# RefloLeo_v1_3.net
KiCad netlist of a schematic drawn in EAGLE
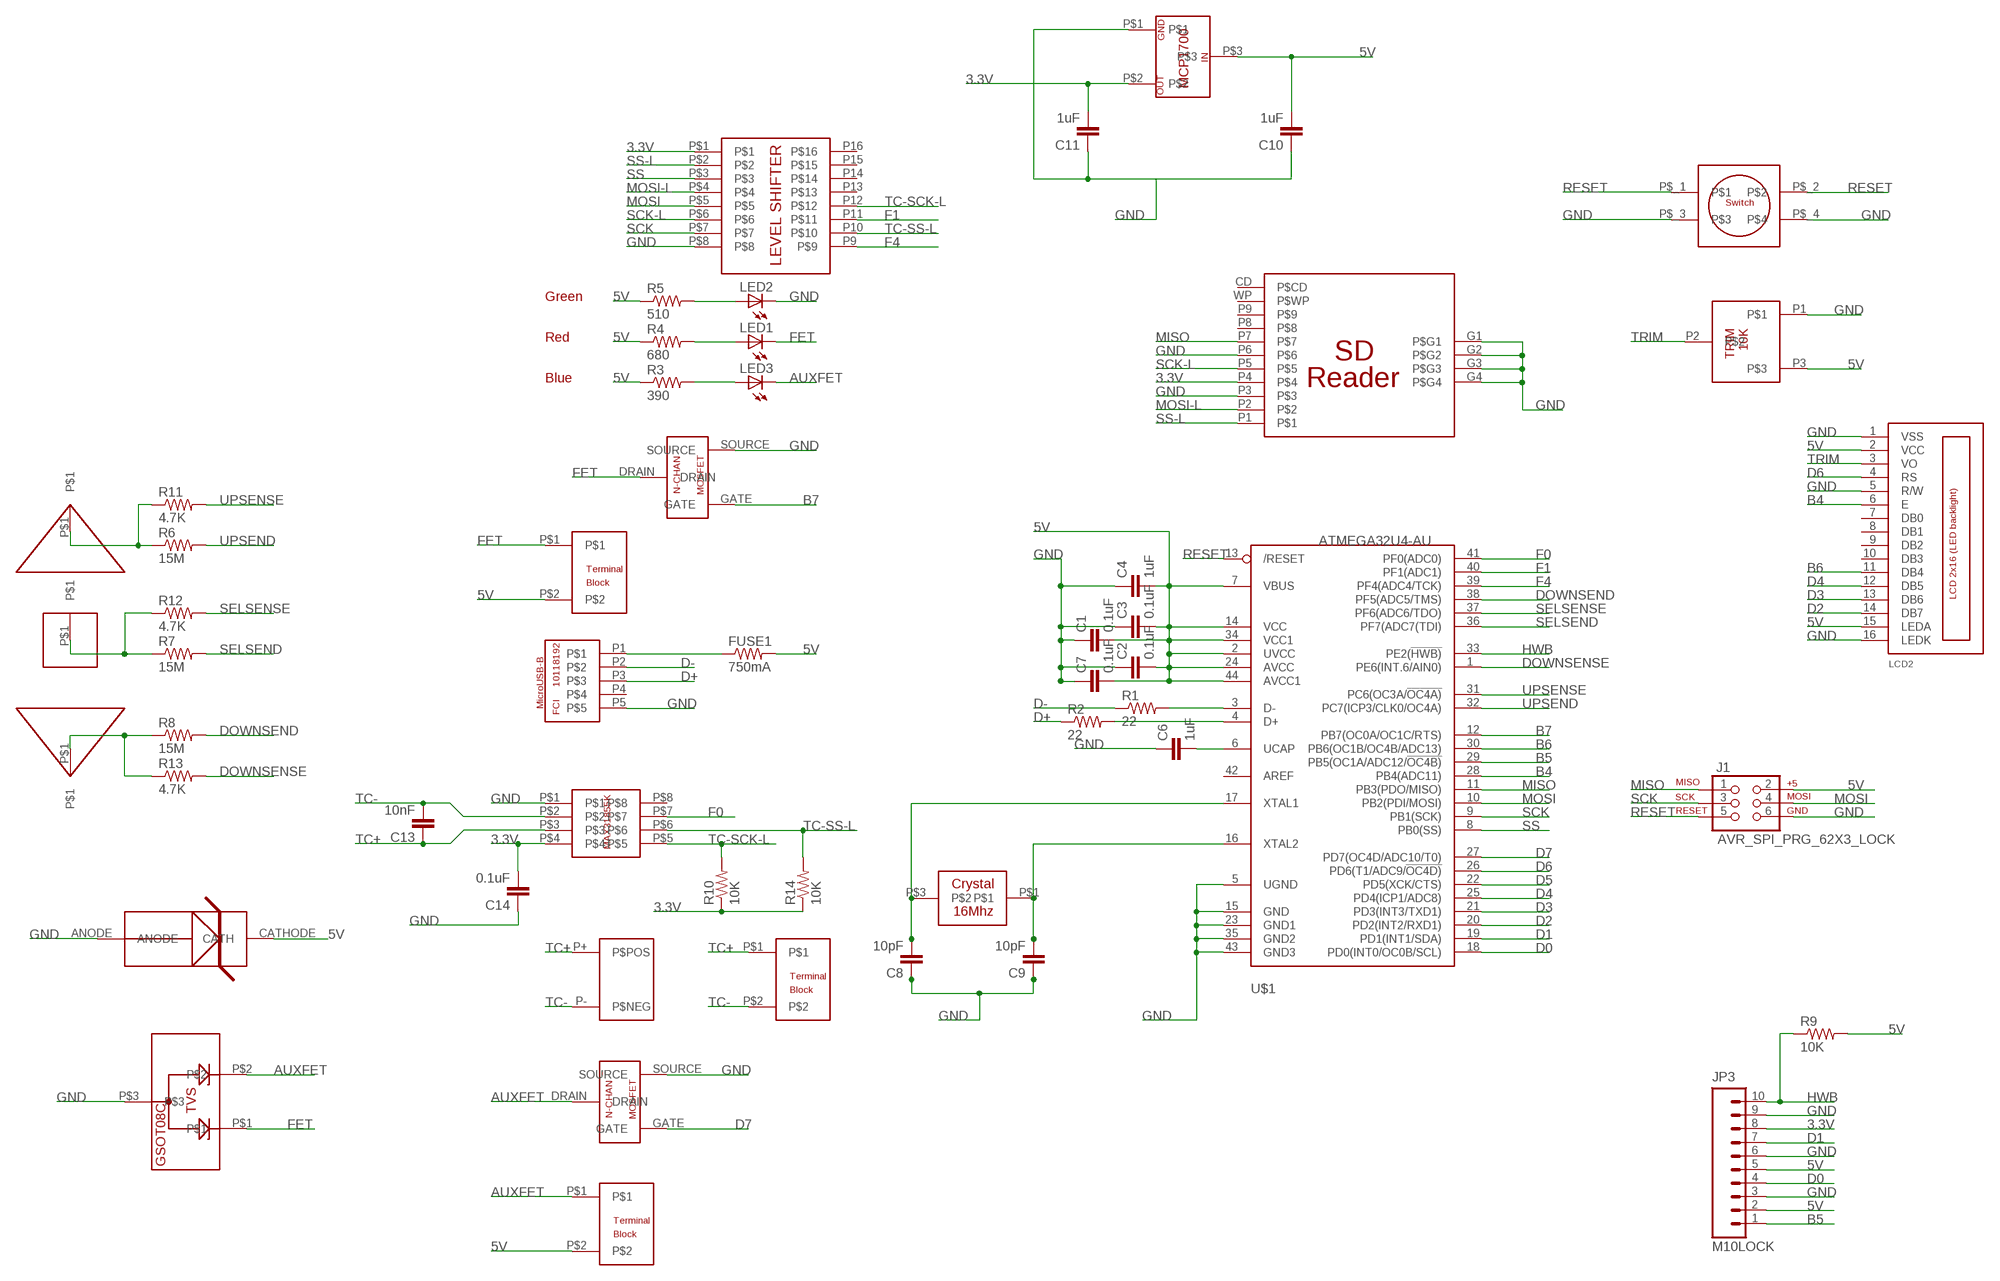
[diagram p0: schematic, sheet 1]

(export (version "E")
  (design (tool "Eeschema 10.0.6"))
  (components
    (comp (ref "C1")
      (value "0.1uF")
      (footprint "eagle-import:0603-CAP")
      (libsource (lib "eagle-import") (part "CAP0603-CAP"))
    )
    (comp (ref "C2")
      (value "0.1uF")
      (footprint "eagle-import:0603-CAP")
      (libsource (lib "eagle-import") (part "CAP0603-CAP"))
    )
    (comp (ref "C3")
      (value "0.1uF")
      (footprint "eagle-import:0603-CAP")
      (libsource (lib "eagle-import") (part "CAP0603-CAP"))
    )
    (comp (ref "C4")
      (value "1uF")
      (footprint "eagle-import:0603-CAP")
      (libsource (lib "eagle-import") (part "CAP0603-CAP"))
    )
    (comp (ref "C6")
      (value "1uF")
      (footprint "eagle-import:0603-CAP")
      (libsource (lib "eagle-import") (part "CAP0603-CAP"))
    )
    (comp (ref "C7")
      (value "0.1uF")
      (footprint "eagle-import:0603-CAP")
      (libsource (lib "eagle-import") (part "CAP0603-CAP"))
    )
    (comp (ref "C8")
      (value "10pF")
      (footprint "eagle-import:0603-CAP")
      (libsource (lib "eagle-import") (part "CAP0603-CAP"))
    )
    (comp (ref "C9")
      (value "10pF")
      (footprint "eagle-import:0603-CAP")
      (libsource (lib "eagle-import") (part "CAP0603-CAP"))
    )
    (comp (ref "C10")
      (value "1uF")
      (footprint "eagle-import:0603-CAP")
      (libsource (lib "eagle-import") (part "CAP0603-CAP"))
    )
    (comp (ref "C11")
      (value "1uF")
      (footprint "eagle-import:0603-CAP")
      (libsource (lib "eagle-import") (part "CAP0603-CAP"))
    )
    (comp (ref "C13")
      (value "10nF")
      (footprint "eagle-import:0603-CAP")
      (libsource (lib "eagle-import") (part "CAP0603-CAP"))
    )
    (comp (ref "C14")
      (value "0.1uF")
      (footprint "eagle-import:0603-CAP")
      (libsource (lib "eagle-import") (part "CAP0603-CAP"))
    )
    (comp (ref "FUSE1")
      (value "750mA")
      (footprint "eagle-import:0603-RES")
      (libsource (lib "eagle-import") (part "RESISTOR0603-RES"))
    )
    (comp (ref "J1")
      (value "AVR_SPI_PRG_62X3_LOCK")
      (footprint "eagle-import:2X3_LOCK")
      (libsource (lib "eagle-import") (part "AVR_SPI_PRG_62X3_LOCK"))
    )
    (comp (ref "JP3")
      (value "M10LOCK")
      (footprint "eagle-import:1X10_LOCK")
      (libsource (lib "eagle-import") (part "M10LOCK"))
    )
    (comp (ref "LCD2")
      (value "LCD_2X16_SIL")
      (footprint "eagle-import:HY-1602F")
      (libsource (lib "eagle-import") (part "LCD_2X16_SIL"))
    )
    (comp (ref "LED1")
      (value "LED0603")
      (footprint "eagle-import:LED-0603")
      (libsource (lib "eagle-import") (part "LED0603"))
    )
    (comp (ref "LED2")
      (value "LED0603")
      (footprint "eagle-import:LED-0603")
      (libsource (lib "eagle-import") (part "LED0603"))
    )
    (comp (ref "LED3")
      (value "LED0603")
      (footprint "eagle-import:LED-0603")
      (libsource (lib "eagle-import") (part "LED0603"))
    )
    (comp (ref "R1")
      (value "22")
      (footprint "eagle-import:0603-RES")
      (libsource (lib "eagle-import") (part "RESISTOR0603-RES"))
    )
    (comp (ref "R2")
      (value "22")
      (footprint "eagle-import:0603-RES")
      (libsource (lib "eagle-import") (part "RESISTOR0603-RES"))
    )
    (comp (ref "R3")
      (value "390")
      (footprint "eagle-import:0603-RES")
      (libsource (lib "eagle-import") (part "RESISTOR0603-RES"))
    )
    (comp (ref "R4")
      (value "680")
      (footprint "eagle-import:0603-RES")
      (libsource (lib "eagle-import") (part "RESISTOR0603-RES"))
    )
    (comp (ref "R5")
      (value "510")
      (footprint "eagle-import:0603-RES")
      (libsource (lib "eagle-import") (part "RESISTOR0603-RES"))
    )
    (comp (ref "R6")
      (value "15M")
      (footprint "eagle-import:0603-RES")
      (libsource (lib "eagle-import") (part "RESISTOR0603-RES"))
    )
    (comp (ref "R7")
      (value "15M")
      (footprint "eagle-import:0603-RES")
      (libsource (lib "eagle-import") (part "RESISTOR0603-RES"))
    )
    (comp (ref "R8")
      (value "15M")
      (footprint "eagle-import:0603-RES")
      (libsource (lib "eagle-import") (part "RESISTOR0603-RES"))
    )
    (comp (ref "R9")
      (value "10K")
      (footprint "eagle-import:0603-RES")
      (libsource (lib "eagle-import") (part "RESISTOR0603-RES"))
    )
    (comp (ref "R10")
      (value "10K")
      (footprint "eagle-import:0603-RES")
      (libsource (lib "eagle-import") (part "RESISTOR0603-RES"))
    )
    (comp (ref "R11")
      (value "4.7K")
      (footprint "eagle-import:0603-RES")
      (libsource (lib "eagle-import") (part "RESISTOR0603-RES"))
    )
    (comp (ref "R12")
      (value "4.7K")
      (footprint "eagle-import:0603-RES")
      (libsource (lib "eagle-import") (part "RESISTOR0603-RES"))
    )
    (comp (ref "R13")
      (value "4.7K")
      (footprint "eagle-import:0603-RES")
      (libsource (lib "eagle-import") (part "RESISTOR0603-RES"))
    )
    (comp (ref "R14")
      (value "10K")
      (footprint "eagle-import:0603-RES")
      (libsource (lib "eagle-import") (part "RESISTOR0603-RES"))
    )
    (comp (ref "U$1")
      (value "ATMEGA32U4-AU")
      (footprint "eagle-import:TQFP44")
      (libsource (lib "eagle-import") (part "ATMEGA32U4-AU"))
    )
    (comp (ref "U$2")
      (value "16MHZ-CRYSTAL_NX3225GA-16.000M-STD-CRG-1")
      (footprint "eagle-import:16MHZ-CRYSTAL_NX3225GA-16.000M-STD-CRG-1")
      (libsource (lib "eagle-import") (part "16MHZ-CRYSTAL_NX3225GA-16.000M-STD-CRG-1"))
    )
    (comp (ref "U$3")
      (value "USB-B_10118192-0001LF")
      (footprint "eagle-import:USB-B_10118192-0001LF")
      (libsource (lib "eagle-import") (part "USB-B_10118192-0001LF"))
    )
    (comp (ref "U$4")
      (value "SDREADER_2041021-4")
      (footprint "eagle-import:SDREADER_2041021-4")
      (libsource (lib "eagle-import") (part "SDREADER_2041021-4"))
    )
    (comp (ref "U$5")
      (value "2POS_TERM_ED2748-ND")
      (footprint "eagle-import:2POS_TERM_ED2748-ND")
      (libsource (lib "eagle-import") (part "2POS_TERM_ED2748-ND"))
    )
    (comp (ref "U$6")
      (value "N-MOSFET630_DMG1012T-7DICT-ND")
      (footprint "eagle-import:N-MOSFET630_DMG1012T-7DICT-ND")
      (libsource (lib "eagle-import") (part "N-MOSFET630_DMG1012T-7DICT-ND"))
    )
    (comp (ref "U$7")
      (value "2POS_TERM_ED2748-ND")
      (footprint "eagle-import:2POS_TERM_ED2748-ND")
      (libsource (lib "eagle-import") (part "2POS_TERM_ED2748-ND"))
    )
    (comp (ref "U$8")
      (value "NXP_LVL_SHIFT_74HC4050D,653")
      (footprint "eagle-import:NXP_LVL_SHIFT_74HC4050D,653")
      (libsource (lib "eagle-import") (part "NXP_LVL_SHIFT_74HC4050D,653"))
    )
    (comp (ref "U$9")
      (value "MAX_TC_MAX31855KASA+")
      (footprint "eagle-import:MAX_TC_MAX31855KASA+")
      (libsource (lib "eagle-import") (part "MAX_TC_MAX31855KASA+"))
    )
    (comp (ref "U$10")
      (value "10K_TRIM_3362F-1-103LF")
      (footprint "eagle-import:10K_TRIM_3362F-1-103LF")
      (libsource (lib "eagle-import") (part "10K_TRIM_3362F-1-103LF"))
    )
    (comp (ref "U$11")
      (value "MCP1700__LDO")
      (footprint "eagle-import:MCP1700__LDO")
      (libsource (lib "eagle-import") (part "MCP1700__LDO"))
    )
    (comp (ref "U$12")
      (value "MOM-SWITCH-EG4620CT-ND")
      (footprint "eagle-import:MOM-SWITCH-EG4620CT-ND")
      (libsource (lib "eagle-import") (part "MOM-SWITCH-EG4620CT-ND"))
    )
    (comp (ref "U$13")
      (value "CAPTOUCH_ARROW")
      (footprint "eagle-import:CAPTOUCH_ARROW")
      (libsource (lib "eagle-import") (part "CAPTOUCH_ARROW"))
    )
    (comp (ref "U$14")
      (value "CAPTOUCH_ARROW")
      (footprint "eagle-import:CAPTOUCH_ARROW")
      (libsource (lib "eagle-import") (part "CAPTOUCH_ARROW"))
    )
    (comp (ref "U$15")
      (value "CAPTOUCH_SQUARE")
      (footprint "eagle-import:CAPTOUCH_SQUARE")
      (libsource (lib "eagle-import") (part "CAPTOUCH_SQUARE"))
    )
    (comp (ref "U$16")
      (value "N-MOSFET630_DMG1012T-7DICT-ND")
      (footprint "eagle-import:N-MOSFET630_DMG1012T-7DICT-ND")
      (libsource (lib "eagle-import") (part "N-MOSFET630_DMG1012T-7DICT-ND"))
    )
    (comp (ref "U$17")
      (value "2POS_TERM_ED2748-ND")
      (footprint "eagle-import:2POS_TERM_ED2748-ND")
      (libsource (lib "eagle-import") (part "2POS_TERM_ED2748-ND"))
    )
    (comp (ref "U$18")
      (value "TVS_DIODE_MATRIX_GSOT08C-GS08")
      (footprint "eagle-import:TVS_DIODE_MATRIX_GSOT08C-GS08")
      (libsource (lib "eagle-import") (part "TVS_DIODE_MATRIX_GSOT08C-GS08"))
    )
    (comp (ref "U$19")
      (value "TVS_DIODE_1CH_1SMB6.0AT3G")
      (footprint "eagle-import:TVS_DIODE_1CH_1SMB6.0AT3G")
      (libsource (lib "eagle-import") (part "TVS_DIODE_1CH_1SMB6.0AT3G"))
    )
    (comp (ref "U$20")
      (value "CUSTOM_K-TYPE")
      (footprint "eagle-import:CUSTOM_K-TYPE")
      (libsource (lib "eagle-import") (part "CUSTOM_K-TYPE"))
    )
  )
  (nets
    (net (code "1") (name "/3.3V") (class "Default")
      (node (ref "C11") (pin "2") (pinfunction "2_2") (pintype "passive"))
      (node (ref "C14") (pin "2") (pinfunction "2_2") (pintype "passive"))
      (node (ref "JP3") (pin "8") (pinfunction "8_8") (pintype "passive"))
      (node (ref "R10") (pin "1") (pinfunction "1_1") (pintype "passive"))
      (node (ref "R14") (pin "1") (pinfunction "1_1") (pintype "passive"))
      (node (ref "U$11") (pin "P$2") (pinfunction "P$2_P$2") (pintype "bidirectional"))
      (node (ref "U$4") (pin "P4") (pinfunction "P$4_P4") (pintype "bidirectional"))
      (node (ref "U$8") (pin "P$1") (pinfunction "P$1_P$1") (pintype "bidirectional"))
      (node (ref "U$9") (pin "P$4") (pinfunction "P$4_P$4") (pintype "bidirectional"))
    )
    (net (code "2") (name "/5V") (class "Default")
      (node (ref "C1") (pin "2") (pinfunction "2_2") (pintype "passive"))
      (node (ref "C10") (pin "2") (pinfunction "2_2") (pintype "passive"))
      (node (ref "C2") (pin "2") (pinfunction "2_2") (pintype "passive"))
      (node (ref "C3") (pin "2") (pinfunction "2_2") (pintype "passive"))
      (node (ref "C4") (pin "2") (pinfunction "2_2") (pintype "passive"))
      (node (ref "C7") (pin "2") (pinfunction "2_2") (pintype "passive"))
      (node (ref "FUSE1") (pin "2") (pinfunction "2_2") (pintype "passive"))
      (node (ref "J1") (pin "2") (pinfunction "2_2") (pintype "passive"))
      (node (ref "JP3") (pin "2") (pinfunction "2_2") (pintype "passive"))
      (node (ref "JP3") (pin "5") (pinfunction "5_5") (pintype "passive"))
      (node (ref "LCD2") (pin "15") (pinfunction "LEDA_15") (pintype "passive"))
      (node (ref "LCD2") (pin "2") (pinfunction "VCC_2") (pintype "power_in"))
      (node (ref "R3") (pin "1") (pinfunction "1_1") (pintype "passive"))
      (node (ref "R4") (pin "1") (pinfunction "1_1") (pintype "passive"))
      (node (ref "R5") (pin "1") (pinfunction "1_1") (pintype "passive"))
      (node (ref "R9") (pin "2") (pinfunction "2_2") (pintype "passive"))
      (node (ref "U$1") (pin "14") (pinfunction "VCC_14") (pintype "bidirectional"))
      (node (ref "U$1") (pin "2") (pinfunction "UVCC_2") (pintype "bidirectional"))
      (node (ref "U$1") (pin "24") (pinfunction "AVCC_24") (pintype "bidirectional"))
      (node (ref "U$1") (pin "34") (pinfunction "VCC1_34") (pintype "bidirectional"))
      (node (ref "U$1") (pin "44") (pinfunction "AVCC1_44") (pintype "bidirectional"))
      (node (ref "U$1") (pin "7") (pinfunction "VBUS_7") (pintype "bidirectional"))
      (node (ref "U$10") (pin "P3") (pinfunction "P$3_P3") (pintype "bidirectional"))
      (node (ref "U$11") (pin "P$3") (pinfunction "P$3_P$3") (pintype "bidirectional"))
      (node (ref "U$17") (pin "P$2") (pinfunction "P$2_P$2") (pintype "bidirectional"))
      (node (ref "U$19") (pin "CATHODE") (pinfunction "CATH_CATHODE") (pintype "bidirectional"))
      (node (ref "U$5") (pin "P$2") (pinfunction "P$2_P$2") (pintype "bidirectional"))
    )
    (net (code "3") (name "/AUXFET") (class "Default")
      (node (ref "LED3") (pin "C") (pinfunction "C_C") (pintype "passive"))
      (node (ref "U$16") (pin "DRAIN") (pinfunction "DRAIN_DRAIN") (pintype "bidirectional"))
      (node (ref "U$17") (pin "P$1") (pinfunction "P$1_P$1") (pintype "bidirectional"))
      (node (ref "U$18") (pin "P$2") (pinfunction "P$2_P$2") (pintype "bidirectional"))
    )
    (net (code "4") (name "/B4") (class "Default")
      (node (ref "LCD2") (pin "6") (pinfunction "E_6") (pintype "input"))
      (node (ref "U$1") (pin "28") (pinfunction "PB4(ADC11)_28") (pintype "bidirectional"))
    )
    (net (code "5") (name "/B5") (class "Default")
      (node (ref "JP3") (pin "1") (pinfunction "1_1") (pintype "passive"))
      (node (ref "U$1") (pin "29") (pinfunction "PB5(OC1A/ADC12/~{OC4B})_29") (pintype "bidirectional"))
    )
    (net (code "6") (name "/B6") (class "Default")
      (node (ref "LCD2") (pin "11") (pinfunction "DB4_11") (pintype "bidirectional"))
      (node (ref "U$1") (pin "30") (pinfunction "PB6(OC1B/OC4B/ADC13)_30") (pintype "bidirectional"))
    )
    (net (code "7") (name "/B7") (class "Default")
      (node (ref "U$1") (pin "12") (pinfunction "PB7(OC0A/OC1C/RTS)_12") (pintype "bidirectional"))
      (node (ref "U$6") (pin "GATE") (pinfunction "GATE_GATE") (pintype "bidirectional"))
    )
    (net (code "8") (name "/D+") (class "Default")
      (node (ref "R2") (pin "1") (pinfunction "1_1") (pintype "passive"))
      (node (ref "U$3") (pin "P3") (pinfunction "P$3_P3") (pintype "bidirectional"))
    )
    (net (code "9") (name "/D-") (class "Default")
      (node (ref "R1") (pin "1") (pinfunction "1_1") (pintype "passive"))
      (node (ref "U$3") (pin "P2") (pinfunction "P$2_P2") (pintype "bidirectional"))
    )
    (net (code "10") (name "/D0") (class "Default")
      (node (ref "JP3") (pin "4") (pinfunction "4_4") (pintype "passive"))
      (node (ref "U$1") (pin "18") (pinfunction "PD0(INT0/OC0B/SCL)_18") (pintype "bidirectional"))
    )
    (net (code "11") (name "/D1") (class "Default")
      (node (ref "JP3") (pin "7") (pinfunction "7_7") (pintype "passive"))
      (node (ref "U$1") (pin "19") (pinfunction "PD1(INT1/SDA)_19") (pintype "bidirectional"))
    )
    (net (code "12") (name "/D2") (class "Default")
      (node (ref "LCD2") (pin "14") (pinfunction "DB7_14") (pintype "bidirectional"))
      (node (ref "U$1") (pin "20") (pinfunction "PD2(INT2/RXD1)_20") (pintype "bidirectional"))
    )
    (net (code "13") (name "/D3") (class "Default")
      (node (ref "LCD2") (pin "13") (pinfunction "DB6_13") (pintype "bidirectional"))
      (node (ref "U$1") (pin "21") (pinfunction "PD3(INT3/TXD1)_21") (pintype "bidirectional"))
    )
    (net (code "14") (name "/D4") (class "Default")
      (node (ref "LCD2") (pin "12") (pinfunction "DB5_12") (pintype "bidirectional"))
      (node (ref "U$1") (pin "25") (pinfunction "PD4(ICP1/ADC8)_25") (pintype "bidirectional"))
    )
    (net (code "15") (name "/D5") (class "Default")
      (node (ref "U$1") (pin "22") (pinfunction "PD5(XCK/CTS)_22") (pintype "bidirectional"))
    )
    (net (code "16") (name "/D6") (class "Default")
      (node (ref "LCD2") (pin "4") (pinfunction "RS_4") (pintype "input"))
      (node (ref "U$1") (pin "26") (pinfunction "PD6(T1/ADC9/~{OC4D})_26") (pintype "bidirectional"))
    )
    (net (code "17") (name "/D7") (class "Default")
      (node (ref "U$1") (pin "27") (pinfunction "PD7(OC4D/ADC10/T0)_27") (pintype "bidirectional"))
      (node (ref "U$16") (pin "GATE") (pinfunction "GATE_GATE") (pintype "bidirectional"))
    )
    (net (code "18") (name "/DOWNSEND") (class "Default")
      (node (ref "R8") (pin "2") (pinfunction "2_2") (pintype "passive"))
      (node (ref "U$1") (pin "38") (pinfunction "PF5(ADC5/TMS)_38") (pintype "bidirectional"))
    )
    (net (code "19") (name "/DOWNSENSE") (class "Default")
      (node (ref "R13") (pin "2") (pinfunction "2_2") (pintype "passive"))
      (node (ref "U$1") (pin "1") (pinfunction "PE6(INT.6/AIN0)_1") (pintype "bidirectional"))
    )
    (net (code "20") (name "/F0") (class "Default")
      (node (ref "U$1") (pin "41") (pinfunction "PF0(ADC0)_41") (pintype "bidirectional"))
      (node (ref "U$9") (pin "P$7") (pinfunction "P$7_P$7") (pintype "bidirectional"))
    )
    (net (code "21") (name "/F1") (class "Default")
      (node (ref "U$1") (pin "40") (pinfunction "PF1(ADC1)_40") (pintype "bidirectional"))
      (node (ref "U$8") (pin "P11") (pinfunction "P$11_P11") (pintype "bidirectional"))
    )
    (net (code "22") (name "/F4") (class "Default")
      (node (ref "U$1") (pin "39") (pinfunction "PF4(ADC4/TCK)_39") (pintype "bidirectional"))
      (node (ref "U$8") (pin "P9") (pinfunction "P$9_P9") (pintype "bidirectional"))
    )
    (net (code "23") (name "/FET") (class "Default")
      (node (ref "LED1") (pin "C") (pinfunction "C_C") (pintype "passive"))
      (node (ref "U$18") (pin "P$1") (pinfunction "P$1_P$1") (pintype "bidirectional"))
      (node (ref "U$5") (pin "P$1") (pinfunction "P$1_P$1") (pintype "bidirectional"))
      (node (ref "U$6") (pin "DRAIN") (pinfunction "DRAIN_DRAIN") (pintype "bidirectional"))
    )
    (net (code "24") (name "/GND") (class "Default")
      (node (ref "C1") (pin "1") (pinfunction "1_1") (pintype "passive"))
      (node (ref "C10") (pin "1") (pinfunction "1_1") (pintype "passive"))
      (node (ref "C11") (pin "1") (pinfunction "1_1") (pintype "passive"))
      (node (ref "C14") (pin "1") (pinfunction "1_1") (pintype "passive"))
      (node (ref "C2") (pin "1") (pinfunction "1_1") (pintype "passive"))
      (node (ref "C3") (pin "1") (pinfunction "1_1") (pintype "passive"))
      (node (ref "C4") (pin "1") (pinfunction "1_1") (pintype "passive"))
      (node (ref "C6") (pin "1") (pinfunction "1_1") (pintype "passive"))
      (node (ref "C7") (pin "1") (pinfunction "1_1") (pintype "passive"))
      (node (ref "C8") (pin "1") (pinfunction "1_1") (pintype "passive"))
      (node (ref "C9") (pin "1") (pinfunction "1_1") (pintype "passive"))
      (node (ref "J1") (pin "6") (pinfunction "6_6") (pintype "passive"))
      (node (ref "JP3") (pin "3") (pinfunction "3_3") (pintype "passive"))
      (node (ref "JP3") (pin "6") (pinfunction "6_6") (pintype "passive"))
      (node (ref "JP3") (pin "9") (pinfunction "9_9") (pintype "passive"))
      (node (ref "LCD2") (pin "1") (pinfunction "VSS_1") (pintype "power_in"))
      (node (ref "LCD2") (pin "16") (pinfunction "LEDK_16") (pintype "passive"))
      (node (ref "LCD2") (pin "5") (pinfunction "R/W_5") (pintype "input"))
      (node (ref "LED2") (pin "C") (pinfunction "C_C") (pintype "passive"))
      (node (ref "U$1") (pin "15") (pinfunction "GND_15") (pintype "bidirectional"))
      (node (ref "U$1") (pin "23") (pinfunction "GND1_23") (pintype "bidirectional"))
      (node (ref "U$1") (pin "35") (pinfunction "GND2_35") (pintype "bidirectional"))
      (node (ref "U$1") (pin "43") (pinfunction "GND3_43") (pintype "bidirectional"))
      (node (ref "U$1") (pin "5") (pinfunction "UGND_5") (pintype "bidirectional"))
      (node (ref "U$10") (pin "P1") (pinfunction "P$1_P1") (pintype "bidirectional"))
      (node (ref "U$11") (pin "P$1") (pinfunction "P$1_P$1") (pintype "bidirectional"))
      (node (ref "U$12") (pin "P$_3") (pinfunction "P$3_P$_3") (pintype "bidirectional"))
      (node (ref "U$12") (pin "P$_4") (pinfunction "P$4_P$_4") (pintype "bidirectional"))
      (node (ref "U$16") (pin "SOURCE") (pinfunction "SOURCE_SOURCE") (pintype "bidirectional"))
      (node (ref "U$18") (pin "P$3") (pinfunction "P$3_P$3") (pintype "bidirectional"))
      (node (ref "U$19") (pin "ANODE") (pinfunction "ANODE_ANODE") (pintype "bidirectional"))
      (node (ref "U$3") (pin "P5") (pinfunction "P$5_P5") (pintype "bidirectional"))
      (node (ref "U$4") (pin "G1") (pinfunction "P$G1_G1") (pintype "bidirectional"))
      (node (ref "U$4") (pin "G2") (pinfunction "P$G2_G2") (pintype "bidirectional"))
      (node (ref "U$4") (pin "G3") (pinfunction "P$G3_G3") (pintype "bidirectional"))
      (node (ref "U$4") (pin "G4") (pinfunction "P$G4_G4") (pintype "bidirectional"))
      (node (ref "U$4") (pin "P3") (pinfunction "P$3_P3") (pintype "bidirectional"))
      (node (ref "U$4") (pin "P6") (pinfunction "P$6_P6") (pintype "bidirectional"))
      (node (ref "U$6") (pin "SOURCE") (pinfunction "SOURCE_SOURCE") (pintype "bidirectional"))
      (node (ref "U$8") (pin "P$8") (pinfunction "P$8_P$8") (pintype "bidirectional"))
      (node (ref "U$9") (pin "P$1") (pinfunction "P$1_P$1") (pintype "bidirectional"))
    )
    (net (code "25") (name "/HWB") (class "Default")
      (node (ref "JP3") (pin "10") (pinfunction "10_10") (pintype "passive"))
      (node (ref "R9") (pin "1") (pinfunction "1_1") (pintype "passive"))
      (node (ref "U$1") (pin "33") (pinfunction "PE2(~{HWB})_33") (pintype "bidirectional"))
    )
    (net (code "26") (name "/MISO") (class "Default")
      (node (ref "J1") (pin "1") (pinfunction "1_1") (pintype "passive"))
      (node (ref "U$1") (pin "11") (pinfunction "PB3(PDO/MISO)_11") (pintype "bidirectional"))
      (node (ref "U$4") (pin "P7") (pinfunction "P$7_P7") (pintype "bidirectional"))
    )
    (net (code "27") (name "/MOSI") (class "Default")
      (node (ref "J1") (pin "4") (pinfunction "4_4") (pintype "passive"))
      (node (ref "U$1") (pin "10") (pinfunction "PB2(PDI/MOSI)_10") (pintype "bidirectional"))
      (node (ref "U$8") (pin "P$5") (pinfunction "P$5_P$5") (pintype "bidirectional"))
    )
    (net (code "28") (name "/MOSI-L") (class "Default")
      (node (ref "U$4") (pin "P2") (pinfunction "P$2_P2") (pintype "bidirectional"))
      (node (ref "U$8") (pin "P$4") (pinfunction "P$4_P$4") (pintype "bidirectional"))
    )
    (net (code "29") (name "/RESET") (class "Default")
      (node (ref "J1") (pin "5") (pinfunction "5_5") (pintype "passive"))
      (node (ref "U$1") (pin "13") (pinfunction "/RESET_13") (pintype "bidirectional"))
      (node (ref "U$12") (pin "P$_1") (pinfunction "P$1_P$_1") (pintype "bidirectional"))
      (node (ref "U$12") (pin "P$_2") (pinfunction "P$2_P$_2") (pintype "bidirectional"))
    )
    (net (code "30") (name "/SCK") (class "Default")
      (node (ref "J1") (pin "3") (pinfunction "3_3") (pintype "passive"))
      (node (ref "U$1") (pin "9") (pinfunction "PB1(SCK)_9") (pintype "bidirectional"))
      (node (ref "U$8") (pin "P$7") (pinfunction "P$7_P$7") (pintype "bidirectional"))
    )
    (net (code "31") (name "/SCK-L") (class "Default")
      (node (ref "U$4") (pin "P5") (pinfunction "P$5_P5") (pintype "bidirectional"))
      (node (ref "U$8") (pin "P$6") (pinfunction "P$6_P$6") (pintype "bidirectional"))
    )
    (net (code "32") (name "/SELSEND") (class "Default")
      (node (ref "R7") (pin "2") (pinfunction "2_2") (pintype "passive"))
      (node (ref "U$1") (pin "36") (pinfunction "PF7(ADC7(TDI)_36") (pintype "bidirectional"))
    )
    (net (code "33") (name "/SELSENSE") (class "Default")
      (node (ref "R12") (pin "2") (pinfunction "2_2") (pintype "passive"))
      (node (ref "U$1") (pin "37") (pinfunction "PF6(ADC6/TDO)_37") (pintype "bidirectional"))
    )
    (net (code "34") (name "/SS") (class "Default")
      (node (ref "U$1") (pin "8") (pinfunction "PB0(SS)_8") (pintype "bidirectional"))
      (node (ref "U$8") (pin "P$3") (pinfunction "P$3_P$3") (pintype "bidirectional"))
    )
    (net (code "35") (name "/SS-L") (class "Default")
      (node (ref "U$4") (pin "P1") (pinfunction "P$1_P1") (pintype "bidirectional"))
      (node (ref "U$8") (pin "P$2") (pinfunction "P$2_P$2") (pintype "bidirectional"))
    )
    (net (code "36") (name "/TC+") (class "Default")
      (node (ref "C13") (pin "1") (pinfunction "1_1") (pintype "passive"))
      (node (ref "U$20") (pin "P+") (pinfunction "P$POS_P+") (pintype "bidirectional"))
      (node (ref "U$7") (pin "P$1") (pinfunction "P$1_P$1") (pintype "bidirectional"))
      (node (ref "U$9") (pin "P$3") (pinfunction "P$3_P$3") (pintype "bidirectional"))
    )
    (net (code "37") (name "/TC-") (class "Default")
      (node (ref "C13") (pin "2") (pinfunction "2_2") (pintype "passive"))
      (node (ref "U$20") (pin "P-") (pinfunction "P$NEG_P-") (pintype "bidirectional"))
      (node (ref "U$7") (pin "P$2") (pinfunction "P$2_P$2") (pintype "bidirectional"))
      (node (ref "U$9") (pin "P$2") (pinfunction "P$2_P$2") (pintype "bidirectional"))
    )
    (net (code "38") (name "/TC-SCK-L") (class "Default")
      (node (ref "R10") (pin "2") (pinfunction "2_2") (pintype "passive"))
      (node (ref "U$8") (pin "P12") (pinfunction "P$12_P12") (pintype "bidirectional"))
      (node (ref "U$9") (pin "P$5") (pinfunction "P$5_P$5") (pintype "bidirectional"))
    )
    (net (code "39") (name "/TC-SS-L") (class "Default")
      (node (ref "R14") (pin "2") (pinfunction "2_2") (pintype "passive"))
      (node (ref "U$8") (pin "P10") (pinfunction "P$10_P10") (pintype "bidirectional"))
      (node (ref "U$9") (pin "P$6") (pinfunction "P$6_P$6") (pintype "bidirectional"))
    )
    (net (code "40") (name "/TRIM") (class "Default")
      (node (ref "LCD2") (pin "3") (pinfunction "VO_3") (pintype "input"))
      (node (ref "U$10") (pin "P2") (pinfunction "P$2_P2") (pintype "bidirectional"))
    )
    (net (code "41") (name "/UPSEND") (class "Default")
      (node (ref "R6") (pin "2") (pinfunction "2_2") (pintype "passive"))
      (node (ref "U$1") (pin "32") (pinfunction "PC7(ICP3/CLK0/OC4A)_32") (pintype "bidirectional"))
    )
    (net (code "42") (name "/UPSENSE") (class "Default")
      (node (ref "R11") (pin "2") (pinfunction "2_2") (pintype "passive"))
      (node (ref "U$1") (pin "31") (pinfunction "PC6(OC3A/~{OC4A})_31") (pintype "bidirectional"))
    )
    (net (code "43") (name "Net-(LED1-PadA)") (class "Default")
      (node (ref "LED1") (pin "A") (pinfunction "A_A") (pintype "passive"))
      (node (ref "R4") (pin "2") (pinfunction "2_2") (pintype "passive"))
    )
    (net (code "44") (name "Net-(LED2-PadA)") (class "Default")
      (node (ref "LED2") (pin "A") (pinfunction "A_A") (pintype "passive"))
      (node (ref "R5") (pin "2") (pinfunction "2_2") (pintype "passive"))
    )
    (net (code "45") (name "Net-(LED3-PadA)") (class "Default")
      (node (ref "LED3") (pin "A") (pinfunction "A_A") (pintype "passive"))
      (node (ref "R3") (pin "2") (pinfunction "2_2") (pintype "passive"))
    )
    (net (code "46") (name "Net-(R11-Pad1)") (class "Default")
      (node (ref "R11") (pin "1") (pinfunction "1_1") (pintype "passive"))
      (node (ref "R6") (pin "1") (pinfunction "1_1") (pintype "passive"))
      (node (ref "U$13") (pin "P$1") (pinfunction "P$1_P$1") (pintype "bidirectional"))
    )
    (net (code "47") (name "Net-(R12-Pad1)") (class "Default")
      (node (ref "R12") (pin "1") (pinfunction "1_1") (pintype "passive"))
      (node (ref "R7") (pin "1") (pinfunction "1_1") (pintype "passive"))
      (node (ref "U$15") (pin "P$1") (pinfunction "P$1_P$1") (pintype "bidirectional"))
    )
    (net (code "48") (name "Net-(R13-Pad1)") (class "Default")
      (node (ref "R13") (pin "1") (pinfunction "1_1") (pintype "passive"))
      (node (ref "R8") (pin "1") (pinfunction "1_1") (pintype "passive"))
      (node (ref "U$14") (pin "P$1") (pinfunction "P$1_P$1") (pintype "bidirectional"))
    )
    (net (code "49") (name "Net-(U$1-D+)") (class "Default")
      (node (ref "R2") (pin "2") (pinfunction "2_2") (pintype "passive"))
      (node (ref "U$1") (pin "4") (pinfunction "D+_4") (pintype "bidirectional"))
    )
    (net (code "50") (name "Net-(U$1-D-)") (class "Default")
      (node (ref "R1") (pin "2") (pinfunction "2_2") (pintype "passive"))
      (node (ref "U$1") (pin "3") (pinfunction "D-_3") (pintype "bidirectional"))
    )
    (net (code "51") (name "Net-(U$1-UCAP)") (class "Default")
      (node (ref "C6") (pin "2") (pinfunction "2_2") (pintype "passive"))
      (node (ref "U$1") (pin "6") (pinfunction "UCAP_6") (pintype "bidirectional"))
    )
    (net (code "52") (name "Net-(U$1-XTAL1)") (class "Default")
      (node (ref "C8") (pin "2") (pinfunction "2_2") (pintype "passive"))
      (node (ref "U$1") (pin "17") (pinfunction "XTAL1_17") (pintype "bidirectional"))
      (node (ref "U$2") (pin "P$3") (pinfunction "P$2_P$3") (pintype "bidirectional"))
    )
    (net (code "53") (name "Net-(U$1-XTAL2)") (class "Default")
      (node (ref "C9") (pin "2") (pinfunction "2_2") (pintype "passive"))
      (node (ref "U$1") (pin "16") (pinfunction "XTAL2_16") (pintype "bidirectional"))
      (node (ref "U$2") (pin "P$1") (pinfunction "P$1_P$1") (pintype "bidirectional"))
    )
    (net (code "54") (name "Net-(U$3-P$1)") (class "Default")
      (node (ref "FUSE1") (pin "1") (pinfunction "1_1") (pintype "passive"))
      (node (ref "U$3") (pin "P1") (pinfunction "P$1_P1") (pintype "bidirectional"))
    )
    (net (code "55") (name "unconnected-(LCD2-DB0-Pad7)") (class "Default")
      (node (ref "LCD2") (pin "7") (pinfunction "DB0_7") (pintype "bidirectional"))
    )
    (net (code "56") (name "unconnected-(LCD2-DB1-Pad8)") (class "Default")
      (node (ref "LCD2") (pin "8") (pinfunction "DB1_8") (pintype "bidirectional"))
    )
    (net (code "57") (name "unconnected-(LCD2-DB2-Pad9)") (class "Default")
      (node (ref "LCD2") (pin "9") (pinfunction "DB2_9") (pintype "bidirectional"))
    )
    (net (code "58") (name "unconnected-(LCD2-DB3-Pad10)") (class "Default")
      (node (ref "LCD2") (pin "10") (pinfunction "DB3_10") (pintype "bidirectional"))
    )
    (net (code "59") (name "unconnected-(U$1-AREF-Pad42)") (class "Default")
      (node (ref "U$1") (pin "42") (pinfunction "AREF_42") (pintype "bidirectional"))
    )
    (net (code "60") (name "unconnected-(U$3-P$4-PadP4)") (class "Default")
      (node (ref "U$3") (pin "P4") (pinfunction "P$4_P4") (pintype "bidirectional"))
    )
    (net (code "61") (name "unconnected-(U$4-P$8-PadP8)") (class "Default")
      (node (ref "U$4") (pin "P8") (pinfunction "P$8_P8") (pintype "bidirectional"))
    )
    (net (code "62") (name "unconnected-(U$4-P$9-PadP9)") (class "Default")
      (node (ref "U$4") (pin "P9") (pinfunction "P$9_P9") (pintype "bidirectional"))
    )
    (net (code "63") (name "unconnected-(U$4-P$CD-PadCD)") (class "Default")
      (node (ref "U$4") (pin "CD") (pinfunction "P$CD_CD") (pintype "bidirectional"))
    )
    (net (code "64") (name "unconnected-(U$4-P$WP-PadWP)") (class "Default")
      (node (ref "U$4") (pin "WP") (pinfunction "P$WP_WP") (pintype "bidirectional"))
    )
    (net (code "65") (name "unconnected-(U$8-P$13-PadP13)") (class "Default")
      (node (ref "U$8") (pin "P13") (pinfunction "P$13_P13") (pintype "bidirectional"))
    )
    (net (code "66") (name "unconnected-(U$8-P$14-PadP14)") (class "Default")
      (node (ref "U$8") (pin "P14") (pinfunction "P$14_P14") (pintype "bidirectional"))
    )
    (net (code "67") (name "unconnected-(U$8-P$15-PadP15)") (class "Default")
      (node (ref "U$8") (pin "P15") (pinfunction "P$15_P15") (pintype "bidirectional"))
    )
    (net (code "68") (name "unconnected-(U$8-P$16-PadP16)") (class "Default")
      (node (ref "U$8") (pin "P16") (pinfunction "P$16_P16") (pintype "bidirectional"))
    )
    (net (code "69") (name "unconnected-(U$9-PadP$8)") (class "Default")
      (node (ref "U$9") (pin "P$8") (pinfunction "P$8_P$8") (pintype "bidirectional"))
    )
  )
)
